# 1_P1.net
KiCad netlist of a schematic drawn in Altium Designer
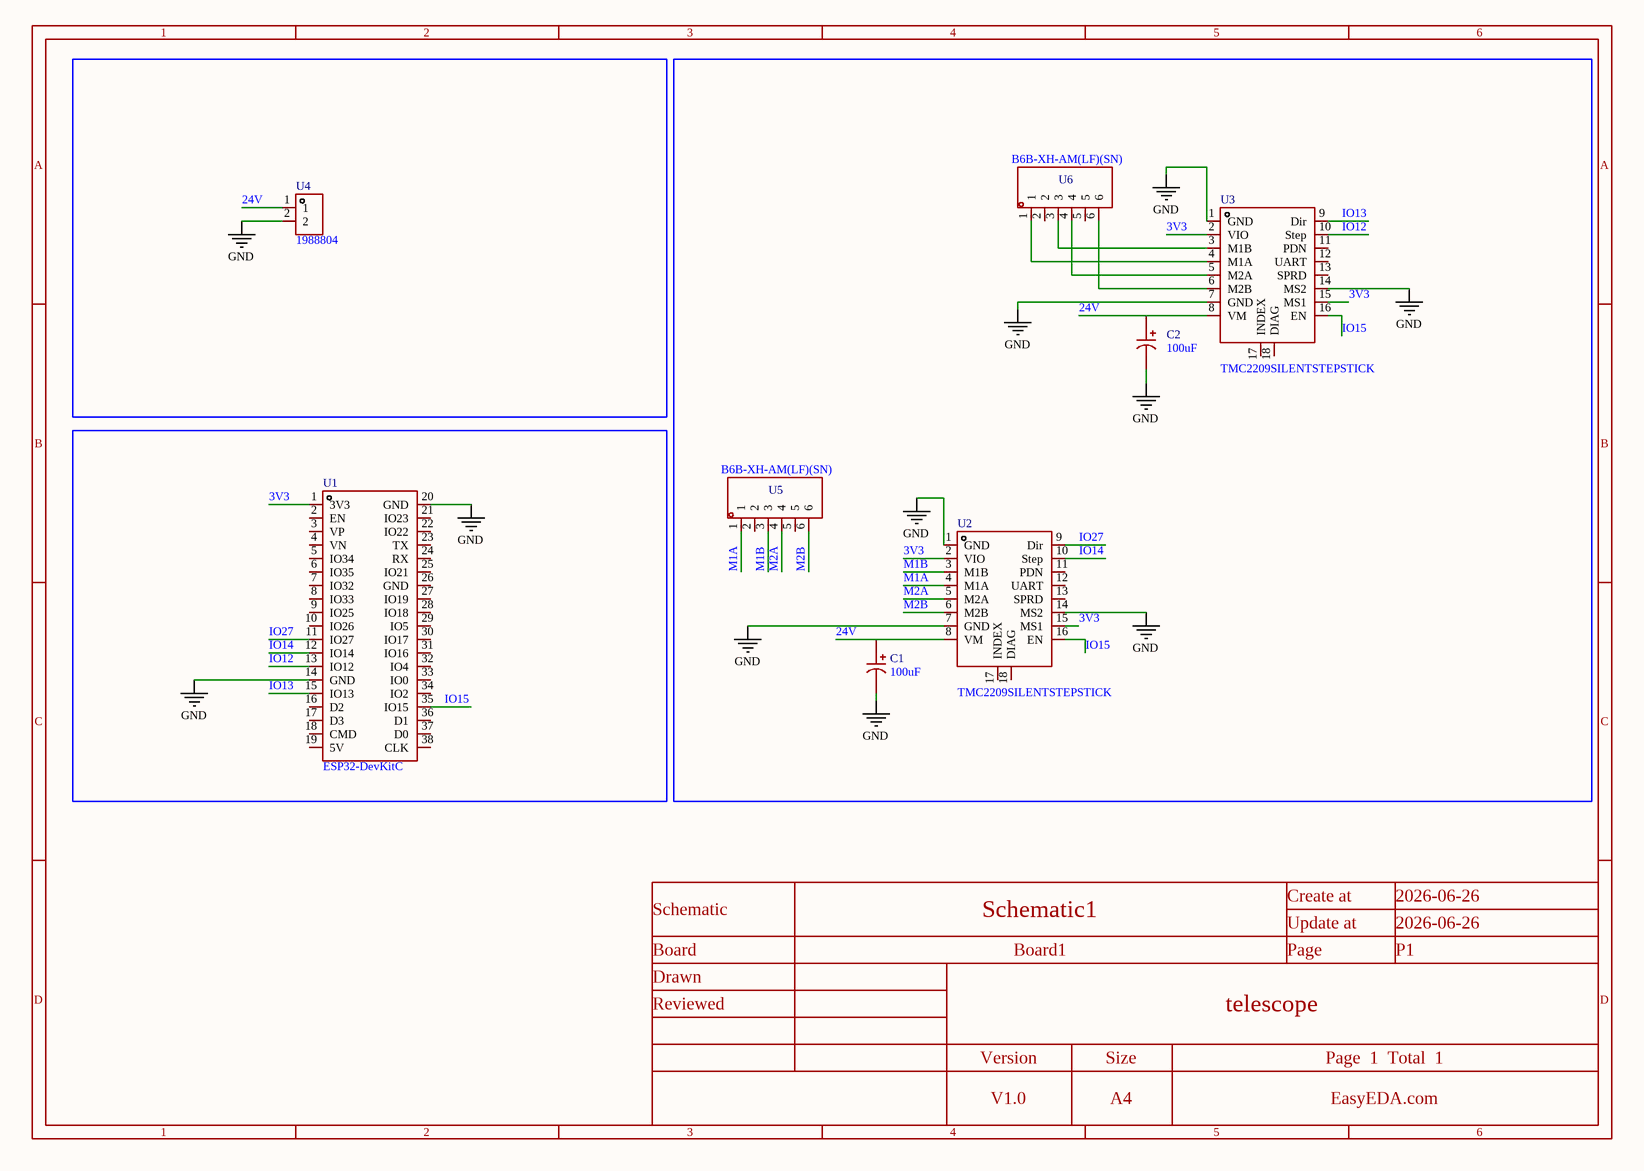
[diagram p0: 1_P1.schdoc]

(export (version "E")
  (design (tool "Eeschema 10.0.6"))
  (components
    (comp (ref "C1")
      (value "100uF")
      (footprint "CAP-TH_BD8.0-P3.50-D0.6-FD-H10.0")
      (fields
        (field (name "MANUFACTURER") "Econd(米朗电子)")
        (field (name "MANUFACTURER PART") "100uF35V8x11GF")
        (field (name "TOLERANCE") "±20%")
      )
      (libsource (lib "altium-import") (part "root_3_100uF35V8x11GF_"))
    )
    (comp (ref "C2")
      (value "100uF")
      (footprint "CAP-TH_BD8.0-P3.50-D0.6-FD-H10.0")
      (fields
        (field (name "MANUFACTURER") "Econd(米朗电子)")
        (field (name "MANUFACTURER PART") "100uF35V8x11GF")
        (field (name "TOLERANCE") "±20%")
      )
      (libsource (lib "altium-import") (part "root_3_100uF35V8x11GF_"))
    )
    (comp (ref "U1")
      (value "ESP32-DevKitC")
      (footprint "BULETM-SMD_ESP32-DEVKITC")
      (fields (field (name "MANUFACTURER") "ESPRESSIF(乐鑫)"))
      (libsource (lib "altium-import") (part "root_0_ESP32-DevKitC_"))
    )
    (comp (ref "U2")
      (value "TMC2209SILENTSTEPSTICK")
      (footprint "COMM-TH_TMC2209SILENTSTEPSTICK")
      (fields (field (name "MANUFACTURER") "TRINAMIC"))
      (libsource (lib "altium-import") (part "root_0_TMC2209SILENTSTEPSTICK_"))
    )
    (comp (ref "U3")
      (value "TMC2209SILENTSTEPSTICK")
      (footprint "COMM-TH_TMC2209SILENTSTEPSTICK")
      (fields (field (name "MANUFACTURER") "TRINAMIC"))
      (libsource (lib "altium-import") (part "root_0_TMC2209SILENTSTEPSTICK_"))
    )
    (comp (ref "U4")
      (value "1988804")
      (footprint "CONN-TH_1988804")
      (fields (field (name "MANUFACTURER") "Phoenix Contact(菲尼克斯)"))
      (libsource (lib "altium-import") (part "root_0_1988804_"))
    )
    (comp (ref "U5")
      (value "B6B-XH-AM(LF)(SN)")
      (footprint "CONN-TH_6P-P2.50_B6B-XH-AM-LF-SN")
      (fields (field (name "MANUFACTURER") "JST"))
      (libsource (lib "altium-import") (part "root_1_B6B-XH-AM(LF)(SN)_"))
    )
    (comp (ref "U6")
      (value "B6B-XH-AM(LF)(SN)")
      (footprint "CONN-TH_6P-P2.50_B6B-XH-AM-LF-SN")
      (fields (field (name "MANUFACTURER") "JST"))
      (libsource (lib "altium-import") (part "root_1_B6B-XH-AM(LF)(SN)_"))
    )
  )
  (nets
    (net (code "1") (name "/3V3") (class "Default")
      (node (ref "U1") (pin "1") (pinfunction "3V3_1") (pintype "passive"))
      (node (ref "U2") (pin "15") (pinfunction "MS1_15") (pintype "passive"))
      (node (ref "U2") (pin "2") (pinfunction "VIO_2") (pintype "passive"))
      (node (ref "U3") (pin "15") (pinfunction "MS1_15") (pintype "passive"))
      (node (ref "U3") (pin "2") (pinfunction "VIO_2") (pintype "passive"))
    )
    (net (code "2") (name "/24V") (class "Default")
      (node (ref "C1") (pin "1") (pinfunction "1_1") (pintype "passive"))
      (node (ref "C2") (pin "1") (pinfunction "1_1") (pintype "passive"))
      (node (ref "U2") (pin "8") (pinfunction "VM_8") (pintype "passive"))
      (node (ref "U3") (pin "8") (pinfunction "VM_8") (pintype "passive"))
      (node (ref "U4") (pin "1") (pinfunction "1_1") (pintype "passive"))
    )
    (net (code "3") (name "/IO12") (class "Default")
      (node (ref "U1") (pin "13") (pinfunction "IO12_13") (pintype "passive"))
      (node (ref "U3") (pin "10") (pinfunction "Step_10") (pintype "passive"))
    )
    (net (code "4") (name "/IO13") (class "Default")
      (node (ref "U1") (pin "15") (pinfunction "IO13_15") (pintype "passive"))
      (node (ref "U3") (pin "9") (pinfunction "Dir_9") (pintype "passive"))
    )
    (net (code "5") (name "/IO14") (class "Default")
      (node (ref "U1") (pin "12") (pinfunction "IO14_12") (pintype "passive"))
      (node (ref "U2") (pin "10") (pinfunction "Step_10") (pintype "passive"))
    )
    (net (code "6") (name "/IO15") (class "Default")
      (node (ref "U1") (pin "35") (pinfunction "IO15_35") (pintype "passive"))
      (node (ref "U2") (pin "16") (pinfunction "EN_16") (pintype "passive"))
      (node (ref "U3") (pin "16") (pinfunction "EN_16") (pintype "passive"))
    )
    (net (code "7") (name "/IO27") (class "Default")
      (node (ref "U1") (pin "11") (pinfunction "IO27_11") (pintype "passive"))
      (node (ref "U2") (pin "9") (pinfunction "Dir_9") (pintype "passive"))
    )
    (net (code "8") (name "/M1A") (class "Default")
      (node (ref "U2") (pin "4") (pinfunction "M1A_4") (pintype "passive"))
      (node (ref "U5") (pin "1") (pinfunction "1_1") (pintype "passive"))
    )
    (net (code "9") (name "/M1B") (class "Default")
      (node (ref "U2") (pin "3") (pinfunction "M1B_3") (pintype "passive"))
      (node (ref "U5") (pin "3") (pinfunction "3_3") (pintype "passive"))
    )
    (net (code "10") (name "/M2A") (class "Default")
      (node (ref "U2") (pin "5") (pinfunction "M2A_5") (pintype "passive"))
      (node (ref "U5") (pin "4") (pinfunction "4_4") (pintype "passive"))
    )
    (net (code "11") (name "/M2B") (class "Default")
      (node (ref "U2") (pin "6") (pinfunction "M2B_6") (pintype "passive"))
      (node (ref "U5") (pin "6") (pinfunction "6_6") (pintype "passive"))
    )
    (net (code "12") (name "GND") (class "Default")
      (node (ref "C1") (pin "2") (pinfunction "2_2") (pintype "passive"))
      (node (ref "C2") (pin "2") (pinfunction "2_2") (pintype "passive"))
      (node (ref "U1") (pin "14") (pinfunction "GND_14") (pintype "passive"))
      (node (ref "U1") (pin "20") (pinfunction "GND_20") (pintype "passive"))
      (node (ref "U2") (pin "1") (pinfunction "GND_1") (pintype "passive"))
      (node (ref "U2") (pin "14") (pinfunction "MS2_14") (pintype "passive"))
      (node (ref "U2") (pin "7") (pinfunction "GND_7") (pintype "passive"))
      (node (ref "U3") (pin "1") (pinfunction "GND_1") (pintype "passive"))
      (node (ref "U3") (pin "14") (pinfunction "MS2_14") (pintype "passive"))
      (node (ref "U3") (pin "7") (pinfunction "GND_7") (pintype "passive"))
      (node (ref "U4") (pin "2") (pinfunction "2_2") (pintype "passive"))
    )
    (net (code "13") (name "Net-(U3-M1A)") (class "Default")
      (node (ref "U3") (pin "4") (pinfunction "M1A_4") (pintype "passive"))
      (node (ref "U6") (pin "1") (pinfunction "1_1") (pintype "passive"))
    )
    (net (code "14") (name "Net-(U3-M1B)") (class "Default")
      (node (ref "U3") (pin "3") (pinfunction "M1B_3") (pintype "passive"))
      (node (ref "U6") (pin "3") (pinfunction "3_3") (pintype "passive"))
    )
    (net (code "15") (name "Net-(U3-M2A)") (class "Default")
      (node (ref "U3") (pin "5") (pinfunction "M2A_5") (pintype "passive"))
      (node (ref "U6") (pin "4") (pinfunction "4_4") (pintype "passive"))
    )
    (net (code "16") (name "Net-(U3-M2B)") (class "Default")
      (node (ref "U3") (pin "6") (pinfunction "M2B_6") (pintype "passive"))
      (node (ref "U6") (pin "6") (pinfunction "6_6") (pintype "passive"))
    )
    (net (code "17") (name "unconnected-(U1-5V-Pad19)") (class "Default")
      (node (ref "U1") (pin "19") (pinfunction "5V_19") (pintype "passive"))
    )
    (net (code "18") (name "unconnected-(U1-CLK-Pad38)") (class "Default")
      (node (ref "U1") (pin "38") (pinfunction "CLK_38") (pintype "passive"))
    )
    (net (code "19") (name "unconnected-(U1-CMD-Pad18)") (class "Default")
      (node (ref "U1") (pin "18") (pinfunction "CMD_18") (pintype "passive"))
    )
    (net (code "20") (name "unconnected-(U1-D0-Pad37)") (class "Default")
      (node (ref "U1") (pin "37") (pinfunction "D0_37") (pintype "passive"))
    )
    (net (code "21") (name "unconnected-(U1-D1-Pad36)") (class "Default")
      (node (ref "U1") (pin "36") (pinfunction "D1_36") (pintype "passive"))
    )
    (net (code "22") (name "unconnected-(U1-D2-Pad16)") (class "Default")
      (node (ref "U1") (pin "16") (pinfunction "D2_16") (pintype "passive"))
    )
    (net (code "23") (name "unconnected-(U1-D3-Pad17)") (class "Default")
      (node (ref "U1") (pin "17") (pinfunction "D3_17") (pintype "passive"))
    )
    (net (code "24") (name "unconnected-(U1-EN-Pad2)") (class "Default")
      (node (ref "U1") (pin "2") (pinfunction "EN_2") (pintype "passive"))
    )
    (net (code "25") (name "unconnected-(U1-GND-Pad26)") (class "Default")
      (node (ref "U1") (pin "26") (pinfunction "GND_26") (pintype "passive"))
    )
    (net (code "26") (name "unconnected-(U1-IO0-Pad33)") (class "Default")
      (node (ref "U1") (pin "33") (pinfunction "IO0_33") (pintype "passive"))
    )
    (net (code "27") (name "unconnected-(U1-IO2-Pad34)") (class "Default")
      (node (ref "U1") (pin "34") (pinfunction "IO2_34") (pintype "passive"))
    )
    (net (code "28") (name "unconnected-(U1-IO4-Pad32)") (class "Default")
      (node (ref "U1") (pin "32") (pinfunction "IO4_32") (pintype "passive"))
    )
    (net (code "29") (name "unconnected-(U1-IO5-Pad29)") (class "Default")
      (node (ref "U1") (pin "29") (pinfunction "IO5_29") (pintype "passive"))
    )
    (net (code "30") (name "unconnected-(U1-IO16-Pad31)") (class "Default")
      (node (ref "U1") (pin "31") (pinfunction "IO16_31") (pintype "passive"))
    )
    (net (code "31") (name "unconnected-(U1-IO17-Pad30)") (class "Default")
      (node (ref "U1") (pin "30") (pinfunction "IO17_30") (pintype "passive"))
    )
    (net (code "32") (name "unconnected-(U1-IO18-Pad28)") (class "Default")
      (node (ref "U1") (pin "28") (pinfunction "IO18_28") (pintype "passive"))
    )
    (net (code "33") (name "unconnected-(U1-IO19-Pad27)") (class "Default")
      (node (ref "U1") (pin "27") (pinfunction "IO19_27") (pintype "passive"))
    )
    (net (code "34") (name "unconnected-(U1-IO21-Pad25)") (class "Default")
      (node (ref "U1") (pin "25") (pinfunction "IO21_25") (pintype "passive"))
    )
    (net (code "35") (name "unconnected-(U1-IO22-Pad22)") (class "Default")
      (node (ref "U1") (pin "22") (pinfunction "IO22_22") (pintype "passive"))
    )
    (net (code "36") (name "unconnected-(U1-IO23-Pad21)") (class "Default")
      (node (ref "U1") (pin "21") (pinfunction "IO23_21") (pintype "passive"))
    )
    (net (code "37") (name "unconnected-(U1-IO25-Pad9)") (class "Default")
      (node (ref "U1") (pin "9") (pinfunction "IO25_9") (pintype "passive"))
    )
    (net (code "38") (name "unconnected-(U1-IO26-Pad10)") (class "Default")
      (node (ref "U1") (pin "10") (pinfunction "IO26_10") (pintype "passive"))
    )
    (net (code "39") (name "unconnected-(U1-IO32-Pad7)") (class "Default")
      (node (ref "U1") (pin "7") (pinfunction "IO32_7") (pintype "passive"))
    )
    (net (code "40") (name "unconnected-(U1-IO33-Pad8)") (class "Default")
      (node (ref "U1") (pin "8") (pinfunction "IO33_8") (pintype "passive"))
    )
    (net (code "41") (name "unconnected-(U1-IO34-Pad5)") (class "Default")
      (node (ref "U1") (pin "5") (pinfunction "IO34_5") (pintype "passive"))
    )
    (net (code "42") (name "unconnected-(U1-IO35-Pad6)") (class "Default")
      (node (ref "U1") (pin "6") (pinfunction "IO35_6") (pintype "passive"))
    )
    (net (code "43") (name "unconnected-(U1-RX-Pad24)") (class "Default")
      (node (ref "U1") (pin "24") (pinfunction "RX_24") (pintype "passive"))
    )
    (net (code "44") (name "unconnected-(U1-TX-Pad23)") (class "Default")
      (node (ref "U1") (pin "23") (pinfunction "TX_23") (pintype "passive"))
    )
    (net (code "45") (name "unconnected-(U1-VN-Pad4)") (class "Default")
      (node (ref "U1") (pin "4") (pinfunction "VN_4") (pintype "passive"))
    )
    (net (code "46") (name "unconnected-(U1-VP-Pad3)") (class "Default")
      (node (ref "U1") (pin "3") (pinfunction "VP_3") (pintype "passive"))
    )
    (net (code "47") (name "unconnected-(U2-DIAG-Pad18)") (class "Default")
      (node (ref "U2") (pin "18") (pinfunction "DIAG_18") (pintype "passive"))
    )
    (net (code "48") (name "unconnected-(U2-INDEX-Pad17)") (class "Default")
      (node (ref "U2") (pin "17") (pinfunction "INDEX_17") (pintype "passive"))
    )
    (net (code "49") (name "unconnected-(U2-PDN-Pad11)") (class "Default")
      (node (ref "U2") (pin "11") (pinfunction "PDN_11") (pintype "passive"))
    )
    (net (code "50") (name "unconnected-(U2-SPRD-Pad13)") (class "Default")
      (node (ref "U2") (pin "13") (pinfunction "SPRD_13") (pintype "passive"))
    )
    (net (code "51") (name "unconnected-(U2-UART-Pad12)") (class "Default")
      (node (ref "U2") (pin "12") (pinfunction "UART_12") (pintype "passive"))
    )
    (net (code "52") (name "unconnected-(U3-DIAG-Pad18)") (class "Default")
      (node (ref "U3") (pin "18") (pinfunction "DIAG_18") (pintype "passive"))
    )
    (net (code "53") (name "unconnected-(U3-INDEX-Pad17)") (class "Default")
      (node (ref "U3") (pin "17") (pinfunction "INDEX_17") (pintype "passive"))
    )
    (net (code "54") (name "unconnected-(U3-PDN-Pad11)") (class "Default")
      (node (ref "U3") (pin "11") (pinfunction "PDN_11") (pintype "passive"))
    )
    (net (code "55") (name "unconnected-(U3-SPRD-Pad13)") (class "Default")
      (node (ref "U3") (pin "13") (pinfunction "SPRD_13") (pintype "passive"))
    )
    (net (code "56") (name "unconnected-(U3-UART-Pad12)") (class "Default")
      (node (ref "U3") (pin "12") (pinfunction "UART_12") (pintype "passive"))
    )
    (net (code "57") (name "unconnected-(U5-Pad2)") (class "Default")
      (node (ref "U5") (pin "2") (pinfunction "2_2") (pintype "passive"))
    )
    (net (code "58") (name "unconnected-(U5-Pad5)") (class "Default")
      (node (ref "U5") (pin "5") (pinfunction "5_5") (pintype "passive"))
    )
    (net (code "59") (name "unconnected-(U6-Pad2)") (class "Default")
      (node (ref "U6") (pin "2") (pinfunction "2_2") (pintype "passive"))
    )
    (net (code "60") (name "unconnected-(U6-Pad5)") (class "Default")
      (node (ref "U6") (pin "5") (pinfunction "5_5") (pintype "passive"))
    )
  )
)
